# 3.net
KiCad netlist of a schematic drawn in Altium Designer
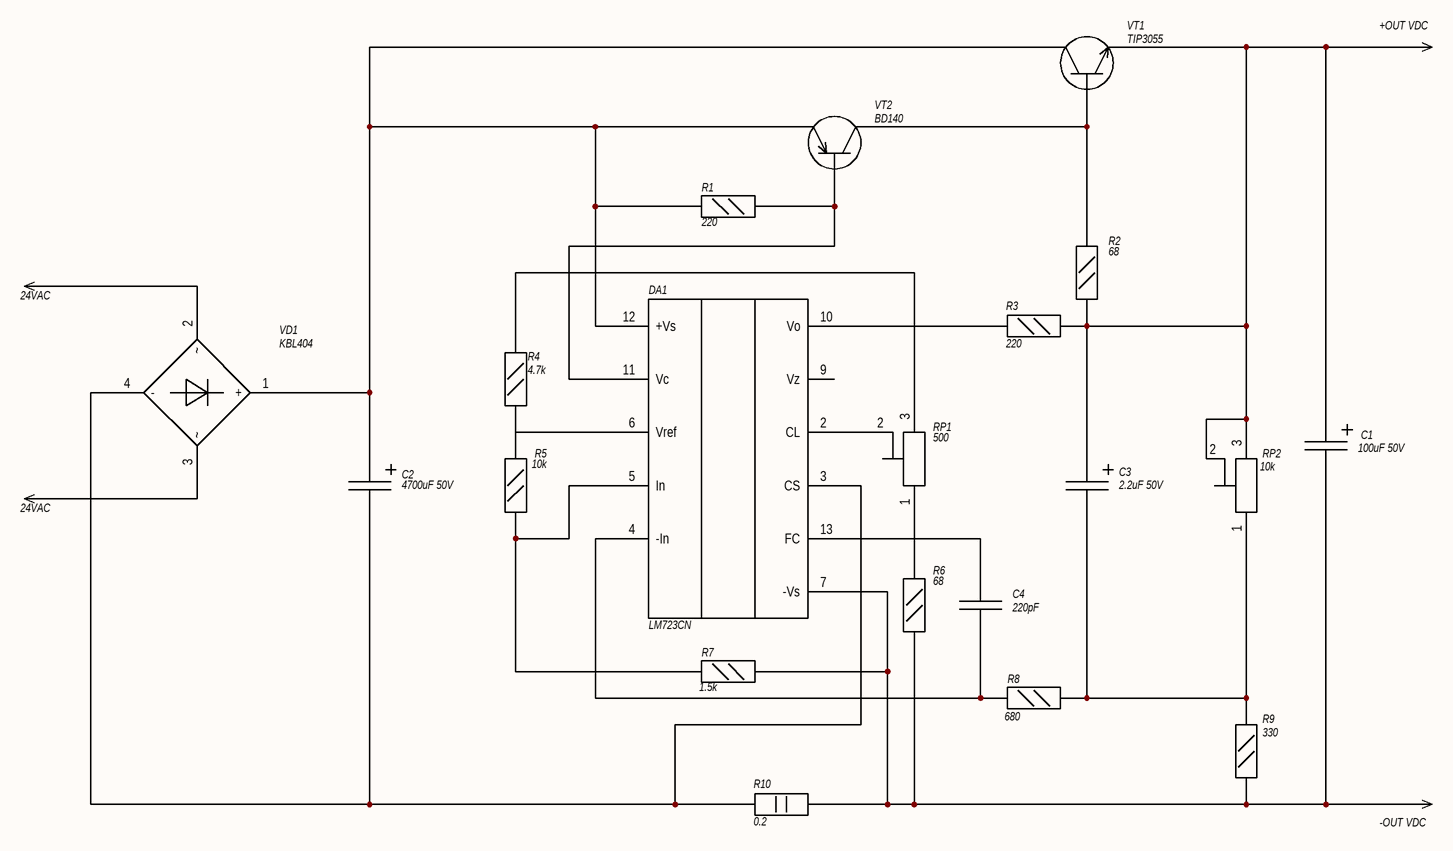
[diagram p0: Э3.SchDoc]

(export (version "E")
  (design (tool "Eeschema 10.0.6"))
  (components
    (comp (ref "C1")
      (value "100uF 50V")
      (footprint "ECAP 100uF 50V")
      (description "Конденсатор электролитический\r\nB41851A6107M000 100мкФ 50В 20%\r\n(EPCOS, Германия)")
      (libsource (lib "LBP") (part "ECAP 100uF 50V"))
    )
    (comp (ref "C2")
      (value "4700uF 50V")
      (footprint "ECAP 4700uF 50V")
      (description "Конденсатор электролитический\r\nB41252C6478M000 4700мкФ 50В 20%\r\n(EPCOS, Германия)")
      (libsource (lib "LBP") (part "ECAP 4700uF 50V"))
    )
    (comp (ref "C3")
      (value "2.2uF 50V")
      (footprint "ECAP 2.2uF 50V")
      (description "Конденсатор электролитический\r\nTKR2R2M2VE11 2.2мкФ 50В 20%\r\n(Jamicon, США)")
      (libsource (lib "LBP") (part "ECAP 2.2uF 50V"))
    )
    (comp (ref "C4")
      (value "220pF")
      (footprint "CAP 220pF")
      (description "Конденсатор керамический\r\nRDE5C1H221J 220пФ 50В 10%\r\n(Murata Electronics, Япония)")
      (libsource (lib "LBP") (part "CAP 220pF"))
    )
    (comp (ref "DA1")
      (value "LM723CN")
      (footprint "Dip14")
      (description "Регулятор напряжения\r\nLM723CN 2В...37В 150мА\r\n(STMicroelectronics, Франция)")
      (libsource (lib "LBP") (part "LM723CN"))
    )
    (comp (ref "O1")
      (value "+OUT VDC")
      (footprint "Connection Pad")
      (libsource (lib "LBP") (part "Connection Pad"))
    )
    (comp (ref "O2")
      (value "24VAC")
      (footprint "Connection Pad")
      (libsource (lib "LBP") (part "Connection Pad"))
    )
    (comp (ref "O3")
      (value "24VAC")
      (footprint "Connection Pad")
      (libsource (lib "LBP") (part "Connection Pad"))
    )
    (comp (ref "O4")
      (value "-OUT VDC")
      (footprint "Connection Pad")
      (libsource (lib "LBP") (part "Connection Pad"))
    )
    (comp (ref "R1")
      (value "220")
      (footprint "Res 0.125W")
      (description "Резистор углеродистый\r\n0.125Вт 220 Ом 5%\r\n(Тайвань)")
      (libsource (lib "LBP") (part "Res 0.125W"))
    )
    (comp (ref "R2")
      (value "68")
      (footprint "Res 0.125W")
      (description "Резистор углеродистый\r\n0.125Вт 68 Ом 5%\r\n(Тайвань)")
      (libsource (lib "LBP") (part "Res 0.125W"))
    )
    (comp (ref "R3")
      (value "220")
      (footprint "Res 0.125W")
      (description "Резистор углеродистый\r\n0.125Вт 220 Ом 5%\r\n(Тайвань)")
      (libsource (lib "LBP") (part "Res 0.125W"))
    )
    (comp (ref "R4")
      (value "4.7k")
      (footprint "Res 0.125W")
      (description "Резистор углеродистый\r\n0.125Вт 4.7 кОм 5%\r\n(Тайвань)")
      (libsource (lib "LBP") (part "Res 0.125W"))
    )
    (comp (ref "R5")
      (value "10k")
      (footprint "Res 0.125W")
      (description "Резистор углеродистый\r\n0.125Вт 10 кОм 5%\r\n(Тайвань)")
      (libsource (lib "LBP") (part "Res 0.125W"))
    )
    (comp (ref "R6")
      (value "68")
      (footprint "Res 0.125W")
      (description "Резистор углеродистый\r\n0.125Вт 68 Ом 5%\r\n(Тайвань)")
      (libsource (lib "LBP") (part "Res 0.125W"))
    )
    (comp (ref "R7")
      (value "1.5k")
      (footprint "Res 0.125W")
      (description "Резистор углеродистый\r\n0.125Вт 1.5 кОм 5%\r\n(Тайвань)")
      (libsource (lib "LBP") (part "Res 0.125W"))
    )
    (comp (ref "R8")
      (value "680")
      (footprint "Res 0.125W")
      (description "Резистор углеродистый\r\n0.125Вт 680 Ом 5%\r\n(Тайвань)")
      (libsource (lib "LBP") (part "Res 0.125W"))
    )
    (comp (ref "R9")
      (value "330")
      (footprint "Res 0.125W")
      (description "Резистор углеродистый\r\n0.125Вт  330 Ом 5%\r\n(Тайвань)")
      (libsource (lib "LBP") (part "Res 0.125W"))
    )
    (comp (ref "R10")
      (value "0.2")
      (footprint "Res 2W")
      (description "Резистор углеродистый\r\n2Вт 0.2 Ом 5%\r\n(Тайвань)")
      (libsource (lib "LBP") (part "Res 2W"))
    )
    (comp (ref "RP1")
      (value "500")
      (footprint "16K1")
      (description "Потенциометр\r\n16K1 0.2Вт 500 Ом 10%")
      (libsource (lib "LBP") (part "Potentiometer"))
    )
    (comp (ref "RP2")
      (value "10k")
      (footprint "16K1")
      (description "Потенциометр\r\n16K1 0.2Вт 10 кОм 10%")
      (libsource (lib "LBP") (part "Potentiometer"))
    )
    (comp (ref "VD1")
      (value "KBL404")
      (footprint "KBL")
      (description "Диодный мост\r\nKDL404 4А 400В")
      (libsource (lib "LBP") (part "KBL404"))
    )
    (comp (ref "VT1")
      (value "TIP3055")
      (footprint "TO-247")
      (description "Транзистор NPN\r\nTIP3055 60В 15А TO-247\r\n(STMicroelectronics, Франция)")
      (libsource (lib "LBP") (part "TIP3055"))
    )
    (comp (ref "VT2")
      (value "BD140")
      (footprint "TO-126")
      (description "Транзистор PNP\r\nBD140 80В 1.5А TO-126\r\n(STMicroelectronics, Франция)")
      (libsource (lib "LBP") (part "BD140"))
    )
  )
  (nets
    (net (code "1") (name "Net-(C3-Pad2)") (class "Default")
      (node (ref "C3") (pin "2") (pinfunction "2_2") (pintype "passive"))
      (node (ref "R8") (pin "1") (pinfunction "1_1") (pintype "passive"))
      (node (ref "R9") (pin "2") (pinfunction "2_2") (pintype "passive"))
      (node (ref "RP2") (pin "1") (pinfunction "1_1") (pintype "passive"))
    )
    (net (code "2") (name "Net-(DA1-+Vs)") (class "Default")
      (node (ref "C2") (pin "1") (pinfunction "1_1") (pintype "passive"))
      (node (ref "DA1") (pin "12") (pinfunction "+Vs_12") (pintype "power_in"))
      (node (ref "R1") (pin "1") (pinfunction "1_1") (pintype "passive"))
      (node (ref "VD1") (pin "1") (pinfunction "+_1") (pintype "passive"))
      (node (ref "VT1") (pin "2") (pinfunction "К_2") (pintype "passive"))
      (node (ref "VT2") (pin "2") (pinfunction "C_2") (pintype "passive"))
    )
    (net (code "3") (name "Net-(DA1--In)") (class "Default")
      (node (ref "C4") (pin "1") (pinfunction "1_1") (pintype "passive"))
      (node (ref "DA1") (pin "4") (pinfunction "-In_4") (pintype "passive"))
      (node (ref "R8") (pin "2") (pinfunction "2_2") (pintype "passive"))
    )
    (net (code "4") (name "Net-(DA1--Vs)") (class "Default")
      (node (ref "C1") (pin "2") (pinfunction "2_2") (pintype "passive"))
      (node (ref "DA1") (pin "7") (pinfunction "-Vs_7") (pintype "power_in"))
      (node (ref "O4") (pin "1") (pinfunction "1_1") (pintype "passive"))
      (node (ref "R10") (pin "2") (pinfunction "2_2") (pintype "passive"))
      (node (ref "R6") (pin "1") (pinfunction "1_1") (pintype "passive"))
      (node (ref "R7") (pin "1") (pinfunction "1_1") (pintype "passive"))
      (node (ref "R9") (pin "1") (pinfunction "1_1") (pintype "passive"))
    )
    (net (code "5") (name "Net-(DA1-CL)") (class "Default")
      (node (ref "DA1") (pin "2") (pinfunction "CL_2") (pintype "passive"))
      (node (ref "RP1") (pin "2") (pinfunction "2_2") (pintype "passive"))
    )
    (net (code "6") (name "Net-(DA1-CS)") (class "Default")
      (node (ref "C2") (pin "2") (pinfunction "2_2") (pintype "passive"))
      (node (ref "DA1") (pin "3") (pinfunction "CS_3") (pintype "passive"))
      (node (ref "R10") (pin "1") (pinfunction "1_1") (pintype "passive"))
      (node (ref "VD1") (pin "4") (pinfunction "-_4") (pintype "passive"))
    )
    (net (code "7") (name "Net-(DA1-FC)") (class "Default")
      (node (ref "C4") (pin "2") (pinfunction "2_2") (pintype "passive"))
      (node (ref "DA1") (pin "13") (pinfunction "FC_13") (pintype "passive"))
    )
    (net (code "8") (name "Net-(DA1-In)") (class "Default")
      (node (ref "DA1") (pin "5") (pinfunction "In_5") (pintype "passive"))
      (node (ref "R5") (pin "1") (pinfunction "1_1") (pintype "passive"))
      (node (ref "R7") (pin "2") (pinfunction "2_2") (pintype "passive"))
    )
    (net (code "9") (name "Net-(DA1-Vc)") (class "Default")
      (node (ref "DA1") (pin "11") (pinfunction "Vc_11") (pintype "passive"))
      (node (ref "R1") (pin "2") (pinfunction "2_2") (pintype "passive"))
      (node (ref "VT2") (pin "1") (pinfunction "B_1") (pintype "passive"))
    )
    (net (code "10") (name "Net-(DA1-Vo)") (class "Default")
      (node (ref "DA1") (pin "10") (pinfunction "Vo_10") (pintype "passive"))
      (node (ref "R3") (pin "2") (pinfunction "2_2") (pintype "passive"))
    )
    (net (code "11") (name "Net-(DA1-Vref)") (class "Default")
      (node (ref "DA1") (pin "6") (pinfunction "Vref_6") (pintype "passive"))
      (node (ref "R4") (pin "1") (pinfunction "1_1") (pintype "passive"))
      (node (ref "R5") (pin "2") (pinfunction "2_2") (pintype "passive"))
    )
    (net (code "12") (name "Net-(O2-Pad1)") (class "Default")
      (node (ref "O2") (pin "1") (pinfunction "1_1") (pintype "passive"))
      (node (ref "VD1") (pin "2") (pinfunction "~_2") (pintype "passive"))
    )
    (net (code "13") (name "Net-(O3-Pad1)") (class "Default")
      (node (ref "O3") (pin "1") (pinfunction "1_1") (pintype "passive"))
      (node (ref "VD1") (pin "3") (pinfunction "~_3") (pintype "passive"))
    )
    (net (code "14") (name "Net-(R4-Pad2)") (class "Default")
      (node (ref "R4") (pin "2") (pinfunction "2_2") (pintype "passive"))
      (node (ref "RP1") (pin "3") (pinfunction "3_3") (pintype "passive"))
    )
    (net (code "15") (name "Net-(R6-Pad2)") (class "Default")
      (node (ref "R6") (pin "2") (pinfunction "2_2") (pintype "passive"))
      (node (ref "RP1") (pin "1") (pinfunction "1_1") (pintype "passive"))
    )
    (net (code "16") (name "Net-(VT1-Б)") (class "Default")
      (node (ref "R2") (pin "2") (pinfunction "2_2") (pintype "passive"))
      (node (ref "VT1") (pin "1") (pinfunction "Б_1") (pintype "passive"))
      (node (ref "VT2") (pin "3") (pinfunction "E_3") (pintype "passive"))
    )
    (net (code "17") (name "Net-(VT1-Э)") (class "Default")
      (node (ref "C1") (pin "1") (pinfunction "1_1") (pintype "passive"))
      (node (ref "C3") (pin "1") (pinfunction "1_1") (pintype "passive"))
      (node (ref "O1") (pin "1") (pinfunction "1_1") (pintype "passive"))
      (node (ref "R2") (pin "1") (pinfunction "1_1") (pintype "passive"))
      (node (ref "R3") (pin "1") (pinfunction "1_1") (pintype "passive"))
      (node (ref "RP2") (pin "2") (pinfunction "2_2") (pintype "passive"))
      (node (ref "RP2") (pin "3") (pinfunction "3_3") (pintype "passive"))
      (node (ref "VT1") (pin "3") (pinfunction "Э_3") (pintype "passive"))
    )
    (net (code "18") (name "unconnected-(DA1-Vz-Pad9)") (class "Default")
      (node (ref "DA1") (pin "9") (pinfunction "Vz_9") (pintype "passive"))
    )
  )
)
